# PowerBreakout.net
KiCad netlist of a schematic drawn in Altium Designer
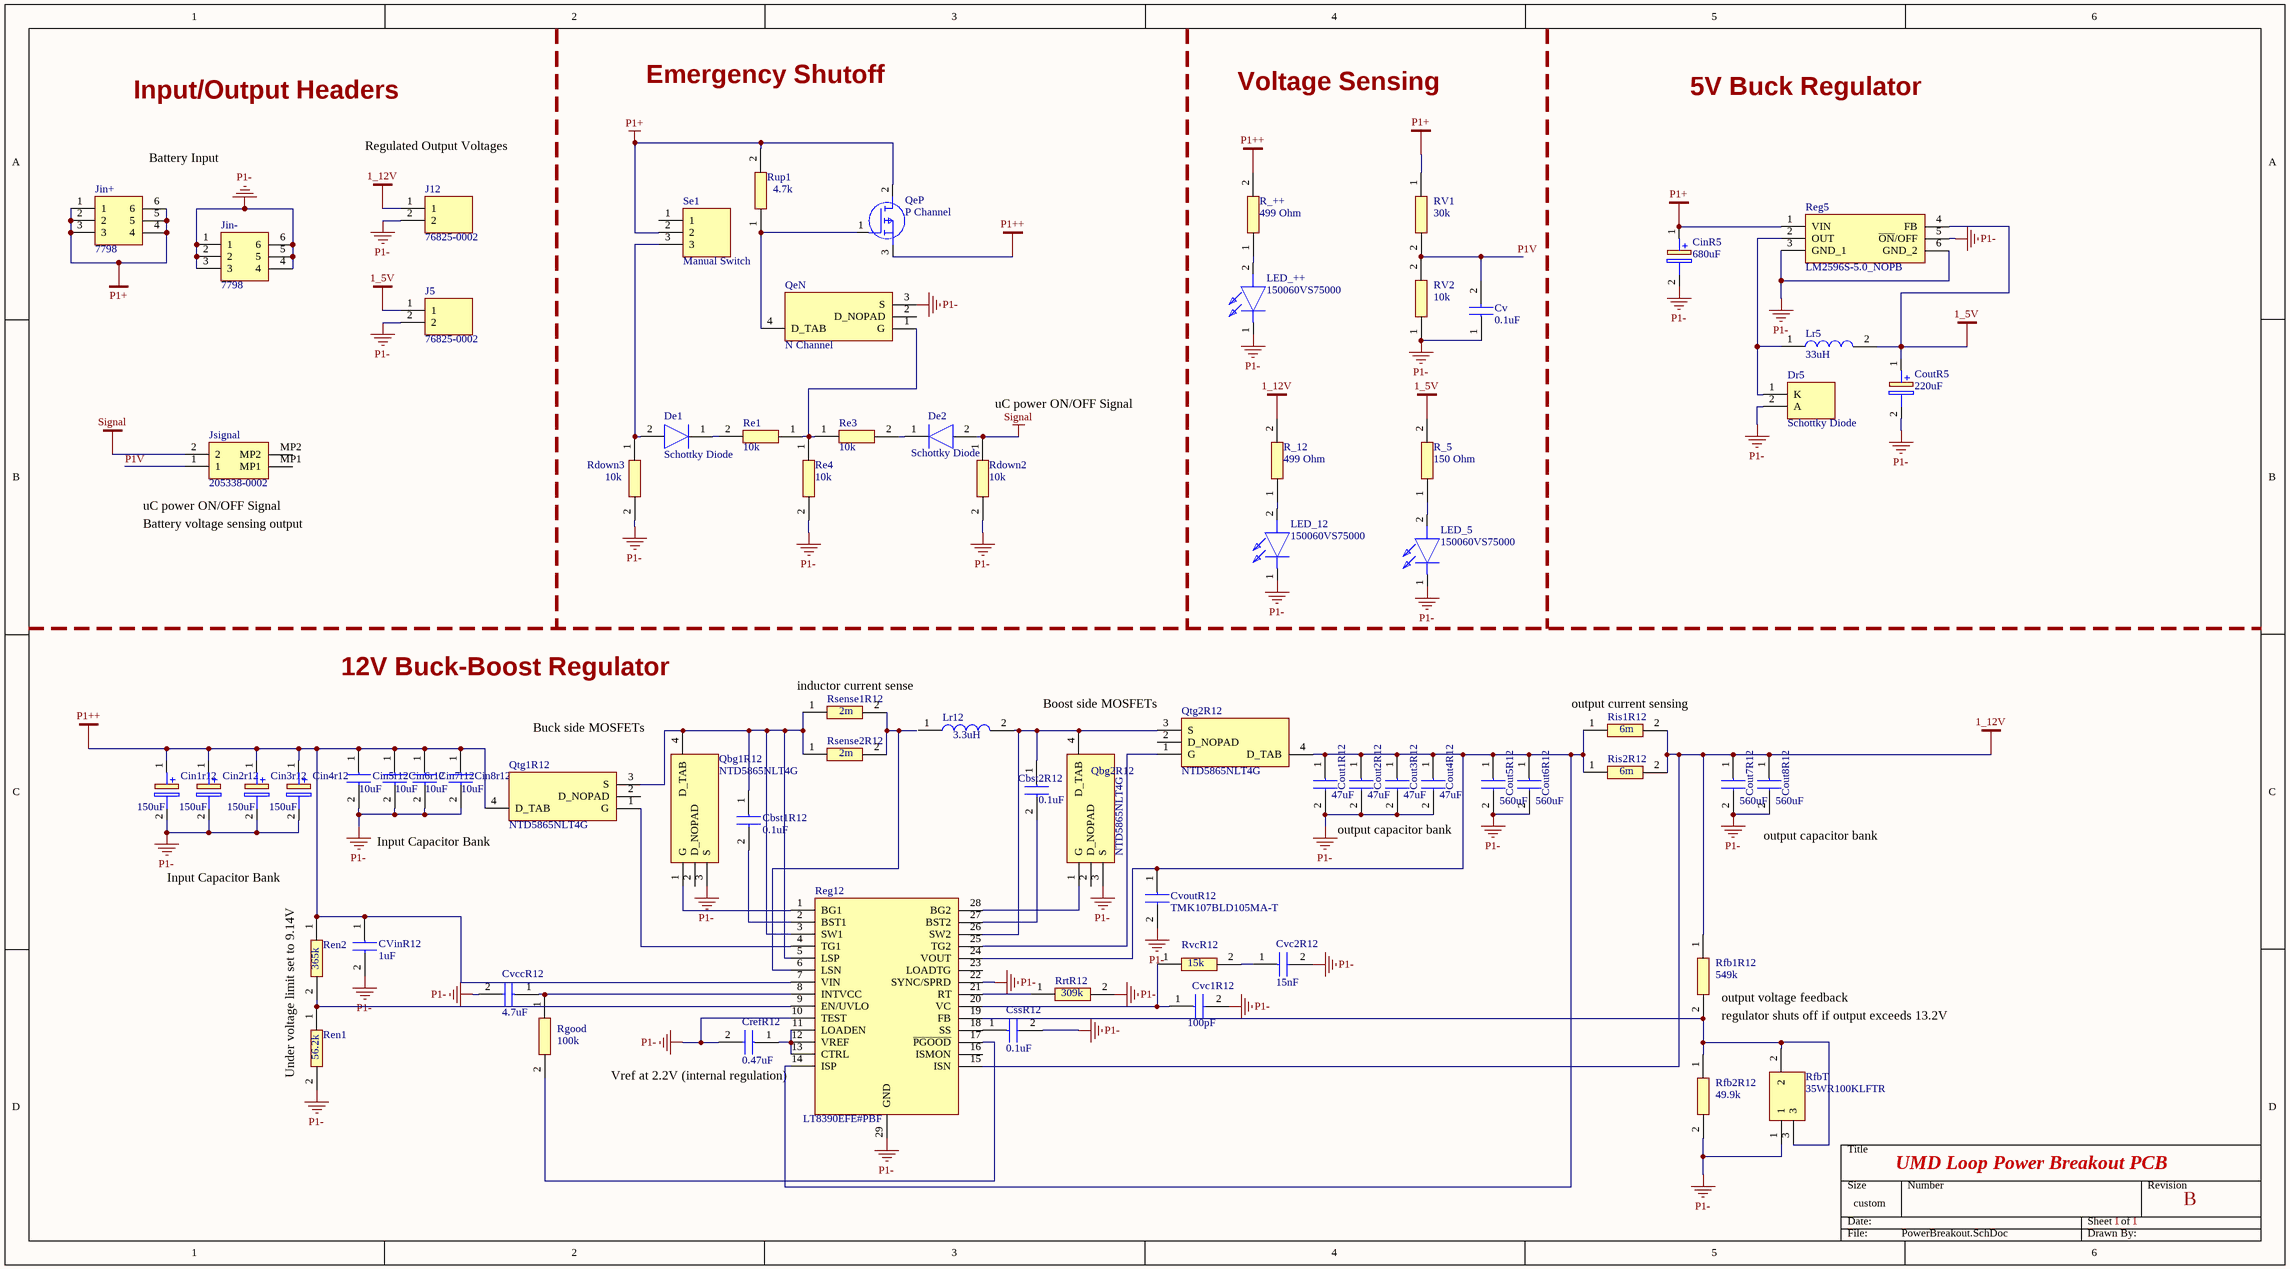
[diagram p0: PowerBreakout.SchDoc]

(export (version "E")
  (design (tool "Eeschema 10.0.6"))
  (components
    (comp (ref "Cbst1R12")
      (value "0.1uF")
      (footprint "PaS_PcbLib:CAPC1608X90N")
      (description "Capacitor")
      (fields
        (field (name "MANUFACTURER_PART_NUMBER") "06033C104J4Z2A")
        (field (name "MOUSER PART NUMBER") "581-06033C104J4Z2A")
      )
      (libsource (lib "PaS_Schlib") (part "06033C104J4Z2A"))
    )
    (comp (ref "Cbst2R12")
      (value "0.1uF")
      (footprint "PaS_PcbLib:CAPC1608X90N")
      (description "Capacitor")
      (fields
        (field (name "MANUFACTURER_PART_NUMBER") "06033C104J4Z2A")
        (field (name "MOUSER PART NUMBER") "581-06033C104J4Z2A")
      )
      (libsource (lib "PaS_Schlib") (part "06033C104J4Z2A"))
    )
    (comp (ref "Cin1r12")
      (value "150uF")
      (footprint "PaS_PcbLib:CAPAE1030X1650N")
      (description "Capacitor Polarised")
      (fields
        (field (name "MANUFACTURER_PART_NUMBER") "EEH-ZS1J151P")
        (field (name "MOUSER PART NUMBER") "667-EEH-ZS1J151P")
      )
      (libsource (lib "PaS_Schlib") (part "EEH-ZS1J151P"))
    )
    (comp (ref "Cin2r12")
      (value "150uF")
      (footprint "PaS_PcbLib:CAPAE1030X1650N")
      (description "Capacitor Polarised")
      (fields
        (field (name "MANUFACTURER_PART_NUMBER") "EEH-ZS1J151P")
        (field (name "MOUSER PART NUMBER") "667-EEH-ZS1J151P")
      )
      (libsource (lib "PaS_Schlib") (part "EEH-ZS1J151P"))
    )
    (comp (ref "Cin3r12")
      (value "150uF")
      (footprint "PaS_PcbLib:CAPAE1030X1650N")
      (description "Capacitor Polarised")
      (fields
        (field (name "MANUFACTURER_PART_NUMBER") "EEH-ZS1J151P")
        (field (name "MOUSER PART NUMBER") "667-EEH-ZS1J151P")
      )
      (libsource (lib "PaS_Schlib") (part "EEH-ZS1J151P"))
    )
    (comp (ref "Cin4r12")
      (value "150uF")
      (footprint "PaS_PcbLib:CAPAE1030X1650N")
      (description "Capacitor Polarised")
      (fields
        (field (name "MANUFACTURER_PART_NUMBER") "EEH-ZS1J151P")
        (field (name "MOUSER PART NUMBER") "667-EEH-ZS1J151P")
      )
      (libsource (lib "PaS_Schlib") (part "EEH-ZS1J151P"))
    )
    (comp (ref "Cin5r12")
      (value "10uF")
      (footprint "PaS_PcbLib:CAPC3225X280N")
      (description "Capacitor")
      (fields
        (field (name "MANUFACTURER_PART_NUMBER") "UMR325AC7106KM-P")
        (field (name "MOUSER PART NUMBER") "963-UMR325AC7106KM-P")
      )
      (libsource (lib "PaS_Schlib") (part "UMR325AC7106KM-P"))
    )
    (comp (ref "Cin6r12")
      (value "10uF")
      (footprint "PaS_PcbLib:CAPC3225X280N")
      (description "Capacitor")
      (fields
        (field (name "MANUFACTURER_PART_NUMBER") "UMR325AC7106KM-P")
        (field (name "MOUSER PART NUMBER") "963-UMR325AC7106KM-P")
      )
      (libsource (lib "PaS_Schlib") (part "UMR325AC7106KM-P"))
    )
    (comp (ref "Cin7r12")
      (value "10uF")
      (footprint "PaS_PcbLib:CAPC3225X280N")
      (description "Capacitor")
      (fields
        (field (name "MANUFACTURER_PART_NUMBER") "UMR325AC7106KM-P")
        (field (name "MOUSER PART NUMBER") "963-UMR325AC7106KM-P")
      )
      (libsource (lib "PaS_Schlib") (part "UMR325AC7106KM-P"))
    )
    (comp (ref "Cin8r12")
      (value "10uF")
      (footprint "PaS_PcbLib:CAPC3225X280N")
      (description "Capacitor")
      (fields
        (field (name "MANUFACTURER_PART_NUMBER") "UMR325AC7106KM-P")
        (field (name "MOUSER PART NUMBER") "963-UMR325AC7106KM-P")
      )
      (libsource (lib "PaS_Schlib") (part "UMR325AC7106KM-P"))
    )
    (comp (ref "CinR5")
      (value "680uF")
      (footprint "PaS_PcbLib:CAPAE1030X1050N")
      (description "Capacitor Polarised")
      (fields
        (field (name "MANUFACTURER_PART_NUMBER") "EEE-FK1C681GP")
        (field (name "MOUSER PART NUMBER") "667-EEE-FK1C681GP")
      )
      (libsource (lib "PaS_Schlib") (part "EEE-FK1C681GP"))
    )
    (comp (ref "Cout1R12")
      (value "47uF")
      (footprint "PaS_PcbLib:CAPC3216X180N")
      (description "Capacitor")
      (fields
        (field (name "MANUFACTURER_PART_NUMBER") "C3216X5R1E476M160AC")
        (field (name "MOUSER PART NUMBER") "810-C3216X5R1E476M")
      )
      (libsource (lib "PaS_Schlib") (part "C3216X5R1E476M160AC"))
    )
    (comp (ref "Cout2R12")
      (value "47uF")
      (footprint "PaS_PcbLib:CAPC3216X180N")
      (description "Capacitor")
      (fields
        (field (name "MANUFACTURER_PART_NUMBER") "C3216X5R1E476M160AC")
        (field (name "MOUSER PART NUMBER") "810-C3216X5R1E476M")
      )
      (libsource (lib "PaS_Schlib") (part "C3216X5R1E476M160AC"))
    )
    (comp (ref "Cout3R12")
      (value "47uF")
      (footprint "PaS_PcbLib:CAPC3216X180N")
      (description "Capacitor")
      (fields
        (field (name "MANUFACTURER_PART_NUMBER") "C3216X5R1E476M160AC")
        (field (name "MOUSER PART NUMBER") "810-C3216X5R1E476M")
      )
      (libsource (lib "PaS_Schlib") (part "C3216X5R1E476M160AC"))
    )
    (comp (ref "Cout4R12")
      (value "47uF")
      (footprint "PaS_PcbLib:CAPC3216X180N")
      (description "Capacitor")
      (fields
        (field (name "MANUFACTURER_PART_NUMBER") "C3216X5R1E476M160AC")
        (field (name "MOUSER PART NUMBER") "810-C3216X5R1E476M")
      )
      (libsource (lib "PaS_Schlib") (part "C3216X5R1E476M160AC"))
    )
    (comp (ref "Cout5R12")
      (value "560uF")
      (footprint "PaS_PcbLib:CAPAE830X1050N")
      (description "Capacitor")
      (fields
        (field (name "MANUFACTURER_PART_NUMBER") "EEE-FT1E561UP")
        (field (name "MOUSER PART NUMBER") "667-EEE-FT1E561UP")
      )
      (libsource (lib "PaS_Schlib") (part "EEE-FT1E561UP"))
    )
    (comp (ref "Cout6R12")
      (value "560uF")
      (footprint "PaS_PcbLib:CAPAE830X1050N")
      (description "Capacitor")
      (fields
        (field (name "MANUFACTURER_PART_NUMBER") "EEE-FT1E561UP")
        (field (name "MOUSER PART NUMBER") "667-EEE-FT1E561UP")
      )
      (libsource (lib "PaS_Schlib") (part "EEE-FT1E561UP"))
    )
    (comp (ref "Cout7R12")
      (value "560uF")
      (footprint "PaS_PcbLib:CAPAE830X1050N")
      (description "Capacitor")
      (fields
        (field (name "MANUFACTURER_PART_NUMBER") "EEE-FT1E561UP")
        (field (name "MOUSER PART NUMBER") "667-EEE-FT1E561UP")
      )
      (libsource (lib "PaS_Schlib") (part "EEE-FT1E561UP"))
    )
    (comp (ref "Cout8R12")
      (value "560uF")
      (footprint "PaS_PcbLib:CAPAE830X1050N")
      (description "Capacitor")
      (fields
        (field (name "MANUFACTURER_PART_NUMBER") "EEE-FT1E561UP")
        (field (name "MOUSER PART NUMBER") "667-EEE-FT1E561UP")
      )
      (libsource (lib "PaS_Schlib") (part "EEE-FT1E561UP"))
    )
    (comp (ref "CoutR5")
      (value "220uF")
      (footprint "PaS_PcbLib:CAPAE660X800N")
      (description "Capacitor Polarised")
      (fields
        (field (name "MANUFACTURER_PART_NUMBER") "EEE-FKA221XAP")
        (field (name "MOUSER PART NUMBER") "667-EEE-FKA221XAP")
      )
      (libsource (lib "PaS_Schlib") (part "EEE-FKA221XAP"))
    )
    (comp (ref "CrefR12")
      (value "0.47uF")
      (footprint "PaS_PcbLib:CAPC2012X140N")
      (description "Capacitor")
      (fields
        (field (name "MANUFACTURER_PART_NUMBER") "08053C474KAT2A")
        (field (name "MOUSER PART NUMBER") "581-08053C474KAT2A")
      )
      (libsource (lib "PaS_Schlib") (part "08053C474KAT2A"))
    )
    (comp (ref "CssR12")
      (value "0.1uF")
      (footprint "PaS_PcbLib:CAPC1608X90N")
      (description "Capacitor")
      (fields
        (field (name "MANUFACTURER_PART_NUMBER") "06033C104J4Z2A")
        (field (name "MOUSER PART NUMBER") "581-06033C104J4Z2A")
      )
      (libsource (lib "PaS_Schlib") (part "06033C104J4Z2A"))
    )
    (comp (ref "Cv")
      (value "0.1uF")
      (footprint "PaS_PcbLib:CAPC2012X100N")
      (description "Capacitor")
      (fields
        (field (name "MANUFACTURER_PART_NUMBER") "C0805C101FCGACAUTO")
        (field (name "MOUSER PART NUMBER") "80-C0805C101FCGACAUT")
      )
      (libsource (lib "PaS_Schlib") (part "C0805C101FCGACAUTO"))
    )
    (comp (ref "Cvc1R12")
      (value "100pF")
      (footprint "PaS_PcbLib:CAPC2012X88N")
      (description "Capacitor")
      (fields
        (field (name "MANUFACTURER_PART_NUMBER") "C0805C101J5RACTU")
        (field (name "MOUSER PART NUMBER") "80-C0805C101J5R")
      )
      (libsource (lib "PaS_Schlib") (part "C0805C101J5RACTU"))
    )
    (comp (ref "Cvc2R12")
      (value "15nF")
      (footprint "PaS_PcbLib:CAPC2012X88N")
      (description "Capacitor")
      (fields
        (field (name "MANUFACTURER_PART_NUMBER") "C0805C151JAGACTU")
        (field (name "MOUSER PART NUMBER") "80-C0805C151JAGACTU")
      )
      (libsource (lib "PaS_Schlib") (part "C0805C151JAGACTU"))
    )
    (comp (ref "CvccR12")
      (value "4.7uF")
      (footprint "PaS_PcbLib:CAPC3316X195N")
      (description "Capacitor")
      (fields
        (field (name "MANUFACTURER_PART_NUMBER") "C1206X475K3RACAUTO7210")
        (field (name "MOUSER PART NUMBER") "80-C1206X475K3RAUTLR")
      )
      (libsource (lib "PaS_Schlib") (part "C1206X475K3RACAUTO7210"))
    )
    (comp (ref "CVinR12")
      (value "1uF")
      (footprint "PaS_PcbLib:CAPC1608X50N")
      (description "Capacitor")
      (fields
        (field (name "MANUFACTURER_PART_NUMBER") "TMK107BLD105MA-T")
        (field (name "MOUSER PART NUMBER") "963-TMK107BLD105MA-T")
      )
      (libsource (lib "PaS_Schlib") (part "TMK107BLD105MA-T"))
    )
    (comp (ref "CvoutR12")
      (value "TMK107BLD105MA-T")
      (footprint "PaS_PcbLib:CAPC1608X50N")
      (description "Capacitor")
      (fields (field (name "MOUSER PART NUMBER") "963-TMK107BLD105MA-T"))
      (libsource (lib "PaS_Schlib") (part "TMK107BLD105MA-T"))
    )
    (comp (ref "De1")
      (value "Schottky Diode")
      (footprint "SODFL3517X110N")
      (description "Diode")
      (fields
        (field (name "MANUFACTURER_PART_NUMBER") "PMEG4030ER,115")
        (field (name "MOUSER PART NUMBER") "771-PMEG4030ER115")
      )
      (libsource (lib "EShutOff") (part "PMEG4030ER,115"))
    )
    (comp (ref "De2")
      (value "Schottky Diode")
      (footprint "SODFL3517X110N")
      (description "Diode")
      (fields
        (field (name "MANUFACTURER_PART_NUMBER") "PMEG4030ER,115")
        (field (name "MOUSER PART NUMBER") "771-PMEG4030ER115")
      )
      (libsource (lib "EShutOff") (part "PMEG4030ER,115"))
    )
    (comp (ref "Dr5")
      (value "Schottky Diode")
      (footprint "SODFL4725X110N")
      (description "Diode")
      (fields
        (field (name "MANUFACTURER_PART_NUMBER") "PMEG4030EP,115")
        (field (name "MOUSER PART NUMBER") "771-PMEG4030EP,115")
      )
      (libsource (lib "PCB_Project") (part "PMEG4030EP,115"))
    )
    (comp (ref "J5")
      (value "76825-0002")
      (footprint "PaS_PcbLib:768250002")
      (description "Connector")
      (fields (field (name "MOUSER PART NUMBER") "538-76825-0002"))
      (libsource (lib "PaS_Schlib") (part "76825-0002"))
    )
    (comp (ref "J12")
      (value "76825-0002")
      (footprint "PaS_PcbLib:768250002")
      (description "Connector")
      (fields (field (name "MOUSER PART NUMBER") "538-76825-0002"))
      (libsource (lib "PaS_Schlib") (part "76825-0002"))
    )
    (comp (ref "Jin+")
      (value "7798")
      (footprint "PaS_PcbLib:7798")
      (description "Connector")
      (fields (field (name "MOUSER PART NUMBER") "534-7798"))
      (libsource (lib "*") (part "7798"))
    )
    (comp (ref "Jin-")
      (value "7798")
      (footprint "PaS_PcbLib:7798")
      (description "Connector")
      (fields (field (name "MOUSER PART NUMBER") "534-7798"))
      (libsource (lib "*") (part "7798"))
    )
    (comp (ref "Jsignal")
      (value "205338-0002")
      (footprint "PaS_PcbLib:2053380002")
      (description "Connector")
      (fields (field (name "MOUSER PART NUMBER") "538-205338-0002"))
      (libsource (lib "*") (part "205338-0002"))
    )
    (comp (ref "LED_++")
      (value "150060VS75000")
      (footprint "PaS_PcbLib:LEDC1608X80N")
      (description "LED")
      (fields (field (name "MOUSER PART NUMBER") "710-150060VS75000"))
      (libsource (lib "*") (part "150060VS75000"))
    )
    (comp (ref "LED_5")
      (value "150060VS75000")
      (footprint "PaS_PcbLib:LEDC1608X80N")
      (description "LED")
      (fields (field (name "MOUSER PART NUMBER") "710-150060VS75000"))
      (libsource (lib "*") (part "150060VS75000"))
    )
    (comp (ref "LED_12")
      (value "150060VS75000")
      (footprint "PaS_PcbLib:LEDC1608X80N")
      (description "LED")
      (fields (field (name "MOUSER PART NUMBER") "710-150060VS75000"))
      (libsource (lib "*") (part "150060VS75000"))
    )
    (comp (ref "Lr5")
      (value "33uH")
      (footprint "PaS_PcbLib:MSS1210333MEB")
      (description "Inductor")
      (fields
        (field (name "MANUFACTURER_PART_NUMBER") "MSS1210-333MEB")
        (field (name "MOUSER PART NUMBER") "994-MSS1210-333MEB")
      )
      (libsource (lib "PaS_Schlib") (part "MSS1210-333MEB"))
    )
    (comp (ref "Lr12")
      (value "3.3uH")
      (footprint "PaS_PcbLib:INDPM135125X650N")
      (description "Inductor")
      (fields
        (field (name "MANUFACTURER_PART_NUMBER") "SRP1265A-3R3M")
        (field (name "MOUSER PART NUMBER") "652-SRP1265A-3R3M")
      )
      (libsource (lib "PaS_Schlib") (part "SRP1265A-3R3M"))
    )
    (comp (ref "Qbg1R12")
      (value "NTD5865NLT4G")
      (footprint "PaS_PcbLib:TO229P990X238-4N")
      (description "Transistor")
      (fields (field (name "MOUSER PART NUMBER") "863-NTD5865NLT4G"))
      (libsource (lib "PaS_Schlib") (part "NTD5865NLT4G"))
    )
    (comp (ref "Qbg2R12")
      (value "NTD5865NLT4G")
      (footprint "PaS_PcbLib:TO229P990X238-4N")
      (description "Transistor")
      (fields (field (name "MOUSER PART NUMBER") "863-NTD5865NLT4G"))
      (libsource (lib "PaS_Schlib") (part "NTD5865NLT4G"))
    )
    (comp (ref "QeN")
      (value "N Channel")
      (footprint "TO229P990X238-4N")
      (description "Transistor")
      (fields
        (field (name "MANUFACTURER_PART_NUMBER") "NTD5865NLT4G")
        (field (name "MOUSER PART NUMBER") "863-NTD5865NLT4G")
      )
      (libsource (lib "") (part "NTD5865NLT4G_1"))
    )
    (comp (ref "QeP")
      (value "P Channel")
      (footprint "STD36P4LLF6")
      (description "MOSFET (P-Channel)")
      (fields
        (field (name "MANUFACTURER_PART_NUMBER") "STD36P4LLF6")
        (field (name "MOUSER PART NUMBER") "511-STD36P4LLF6")
      )
      (libsource (lib "EShutOff") (part "STD36P4LLF6"))
    )
    (comp (ref "Qtg1R12")
      (value "NTD5865NLT4G")
      (footprint "PaS_PcbLib:TO229P990X238-4N")
      (description "Transistor")
      (fields (field (name "MOUSER PART NUMBER") "863-NTD5865NLT4G"))
      (libsource (lib "") (part "NTD5865NLT4G_1"))
    )
    (comp (ref "Qtg2R12")
      (value "NTD5865NLT4G")
      (footprint "PaS_PcbLib:TO229P990X238-4N")
      (description "Transistor")
      (fields (field (name "MOUSER PART NUMBER") "863-NTD5865NLT4G"))
      (libsource (lib "PaS_Schlib") (part "NTD5865NLT4G"))
    )
    (comp (ref "Rdown2")
      (value "10k")
      (footprint "RESC2012X60N")
      (description "Resistor")
      (fields
        (field (name "MANUFACTURER_PART_NUMBER") "CHP0805-FX-1002ELF")
        (field (name "MOUSER PART NUMBER") "652-CHP0805FX1002ELF")
      )
      (libsource (lib "") (part "CHP0805-FX-1002ELF_1"))
    )
    (comp (ref "Rdown3")
      (value "10k")
      (footprint "RESC2012X60N")
      (description "Resistor")
      (fields
        (field (name "MANUFACTURER_PART_NUMBER") "CHP0805-FX-1002ELF")
        (field (name "MOUSER PART NUMBER") "652-CHP0805FX1002ELF")
      )
      (libsource (lib "") (part "CHP0805-FX-1002ELF_1"))
    )
    (comp (ref "Re1")
      (value "10k")
      (footprint "RESC2012X60N")
      (description "Resistor")
      (fields
        (field (name "MANUFACTURER_PART_NUMBER") "CHP0805-FX-1002ELF")
        (field (name "MOUSER PART NUMBER") "652-CHP0805FX1002ELF")
      )
      (libsource (lib "EShutOff") (part "CHP0805-FX-1002ELF"))
    )
    (comp (ref "Re3")
      (value "10k")
      (footprint "RESC2012X60N")
      (description "Resistor")
      (fields
        (field (name "MANUFACTURER_PART_NUMBER") "CHP0805-FX-1002ELF")
        (field (name "MOUSER PART NUMBER") "652-CHP0805FX1002ELF")
      )
      (libsource (lib "") (part "CHP0805-FX-1002ELF_2"))
    )
    (comp (ref "Re4")
      (value "10k")
      (footprint "RESC2012X60N")
      (description "Resistor")
      (fields
        (field (name "MANUFACTURER_PART_NUMBER") "CHP0805-FX-1002ELF")
        (field (name "MOUSER PART NUMBER") "652-CHP0805FX1002ELF")
      )
      (libsource (lib "") (part "CHP0805-FX-1002ELF_1"))
    )
    (comp (ref "Reg5")
      (value "LM2596S-5.0_NOPB")
      (footprint "PaS_PcbLib:KTT0005B")
      (description "Integrated Circuit")
      (fields
        (field (name "MANUFACTURER_PART_NUMBER") "LM2596S-5.0/NOPB")
        (field (name "MOUSER PART NUMBER") "926-LM2596S-5.0/NOPB")
      )
      (libsource (lib "PaS_Schlib") (part "LM2596S-5.0_NOPB"))
    )
    (comp (ref "Reg12")
      (value "LT8390EFE#PBF")
      (footprint "PaS_PcbLib:SOP65P640X120-29N")
      (description "Integrated Circuit")
      (fields (field (name "MOUSER PART NUMBER") "584-LT8390EFE#PBF"))
      (libsource (lib "PaS_Schlib") (part "LT8390EFE#PBF"))
    )
    (comp (ref "Ren1")
      (value "56.2k")
      (footprint "PaS_PcbLib:RESC3216X60N")
      (description "Resistor")
      (fields
        (field (name "MANUFACTURER_PART_NUMBER") "CRCW120656K2FKEA")
        (field (name "MOUSER PART NUMBER") "71-CRCW1206-56.2K-E3")
      )
      (libsource (lib "PaS_Schlib") (part "CRCW120656K2FKEA"))
    )
    (comp (ref "Ren2")
      (value "365k")
      (footprint "PaS_PcbLib:RESC1608X55N")
      (description "Resistor")
      (fields
        (field (name "MANUFACTURER_PART_NUMBER") "CR0603-FX-3653ELF")
        (field (name "MOUSER PART NUMBER") "652-CR0603FX-3653ELF")
      )
      (libsource (lib "PaS_Schlib") (part "CR0603-FX-3653ELF"))
    )
    (comp (ref "Rfb1R12")
      (value "549k")
      (footprint "PaS_PcbLib:RESC2012X65N")
      (description "Resistor")
      (fields
        (field (name "MANUFACTURER_PART_NUMBER") "RP73D2A1M0BTDF")
        (field (name "MOUSER PART NUMBER") "279-RP73D2A1M0BTDF")
      )
      (libsource (lib "PaS_Schlib") (part "RP73D2A1M0BTDF"))
    )
    (comp (ref "Rfb2R12")
      (value "49.9k")
      (footprint "PaS_PcbLib:RESC2113X66N")
      (description "Resistor")
      (fields
        (field (name "MANUFACTURER_PART_NUMBER") "PFC-W0805LF-03-1073-B")
        (field (name "MOUSER PART NUMBER") "66-PFC08LF107K-B")
      )
      (libsource (lib "PaS_Schlib") (part "PFC-W0805LF-03-1073-B"))
    )
    (comp (ref "RfbT")
      (value "35WR100KLFTR")
      (footprint "PaS_PcbLib:35WR100KLFTR")
      (description "Variable Resistor")
      (fields (field (name "MOUSER PART NUMBER") "858-35WR100KLFTR"))
      (libsource (lib "*") (part "35WR100KLFTR"))
    )
    (comp (ref "Rgood")
      (value "100k")
      (footprint "PaS_PcbLib:RESC3116X65N")
      (description "Resistor")
      (fields
        (field (name "MANUFACTURER_PART_NUMBER") "CMP1206AFX-5601ELF")
        (field (name "MOUSER PART NUMBER") "652-CMP1206AFX-5601L")
      )
      (libsource (lib "PaS_Schlib") (part "CMP1206AFX-5601ELF"))
    )
    (comp (ref "Ris1R12")
      (value "6m")
      (footprint "PaS_PcbLib:FUSC6432X52N")
      (description "Resistor")
      (fields
        (field (name "MANUFACTURER_PART_NUMBER") "PMR100HZPFU6L00")
        (field (name "MOUSER PART NUMBER") "755-PMR100HZPFU6L00")
      )
      (libsource (lib "PaS_Schlib") (part "PMR100HZPFU6L00"))
    )
    (comp (ref "Ris2R12")
      (value "6m")
      (footprint "PaS_PcbLib:FUSC6432X52N")
      (description "Resistor")
      (fields
        (field (name "MANUFACTURER_PART_NUMBER") "PMR100HZPFU6L00")
        (field (name "MOUSER PART NUMBER") "755-PMR100HZPFU6L00")
      )
      (libsource (lib "PaS_Schlib") (part "PMR100HZPFU6L00"))
    )
    (comp (ref "RrtR12")
      (value "309k")
      (footprint "PaS_PcbLib:RESC2012X70N")
      (description "Resistor")
      (fields
        (field (name "MANUFACTURER_PART_NUMBER") "ERJ-6ENF3093V")
        (field (name "MOUSER PART NUMBER") "667-ERJ-6ENF3093V")
      )
      (libsource (lib "PaS_Schlib") (part "ERJ-6ENF3093V"))
    )
    (comp (ref "Rsense1R12")
      (value "2m")
      (footprint "PaS_PcbLib:RESC6432X70N")
      (description "Resistor")
      (fields
        (field (name "MANUFACTURER_PART_NUMBER") "ULRB22512R002FLFSLT")
        (field (name "MOUSER PART NUMBER") "66-ULRB2R002FLFSLT")
      )
      (libsource (lib "PaS_Schlib") (part "ULRB22512R002FLFSLT"))
    )
    (comp (ref "Rsense2R12")
      (value "2m")
      (footprint "PaS_PcbLib:RESC6432X70N")
      (description "Resistor")
      (fields
        (field (name "MANUFACTURER_PART_NUMBER") "ULRB22512R002FLFSLT")
        (field (name "MOUSER PART NUMBER") "66-ULRB2R002FLFSLT")
      )
      (libsource (lib "PaS_Schlib") (part "ULRB22512R002FLFSLT"))
    )
    (comp (ref "Rup1")
      (value "4.7k")
      (footprint "RESC3116X65N")
      (description "Resistor")
      (fields
        (field (name "MANUFACTURER_PART_NUMBER") "CHP1206AFX-4701ELF")
        (field (name "MOUSER PART NUMBER") "652-CHP1206AFX-4701L")
      )
      (libsource (lib "EShutOff") (part "CHP1206AFX-4701ELF"))
    )
    (comp (ref "RV1")
      (value "30k")
      (footprint "PaS_PcbLib:RESC2012X60N")
      (description "Resistor")
      (fields
        (field (name "MANUFACTURER_PART_NUMBER") "CRCW080530K0FKEAC")
        (field (name "MOUSER PART NUMBER") "71-CRCW080530K0FKEAC")
      )
      (libsource (lib "PaS_Schlib") (part "CRCW080530K0FKEAC"))
    )
    (comp (ref "RV2")
      (value "10k")
      (footprint "PaS_PcbLib:RESC2012X60N")
      (description "Resistor")
      (fields
        (field (name "MANUFACTURER_PART_NUMBER") "CHP0805-FX-1002ELF")
        (field (name "MOUSER PART NUMBER") "652-CHP0805FX1002ELF")
      )
      (libsource (lib "PaS_Schlib") (part "CHP0805-FX-1002ELF"))
    )
    (comp (ref "RvcR12")
      (value "15k")
      (footprint "PaS_PcbLib:RESC1608X55N")
      (description "Resistor")
      (fields
        (field (name "MANUFACTURER_PART_NUMBER") "ERA-3VEB1502V")
        (field (name "MOUSER PART NUMBER") "667-ERA-3VEB1502V")
      )
      (libsource (lib "PaS_Schlib") (part "ERA-3VEB1502V"))
    )
    (comp (ref "R_++")
      (value "499 Ohm")
      (footprint "PaS_PcbLib:RESC2012X60N")
      (description "Resistor")
      (fields (field (name "MANUFACTURER_PART_NUMBER") "RK73H2ATTD4990F"))
      (libsource (lib "*") (part "RK73H2ATTD4990F"))
    )
    (comp (ref "R_5")
      (value "150 Ohm")
      (footprint "PaS_PcbLib:RESC2012X60N")
      (description "Resistor")
      (fields
        (field (name "MANUFACTURER_PART_NUMBER") "RK73H2ATTD1500F")
        (field (name "MOUSER PART NUMBER") "660-RK73H2ATTD1500F")
      )
      (libsource (lib "*") (part "RK73H2ATTD1500F"))
    )
    (comp (ref "R_12")
      (value "499 Ohm")
      (footprint "PaS_PcbLib:RESC2012X60N")
      (description "Resistor")
      (fields (field (name "MANUFACTURER_PART_NUMBER") "RK73H2ATTD4990F"))
      (libsource (lib "*") (part "RK73H2ATTD4990F"))
    )
    (comp (ref "Se1")
      (value "Manual Switch")
      (footprint "2M1SP3T1B1M2QE")
      (description "Switch")
      (fields
        (field (name "MANUFACTURER_PART_NUMBER") "2M1-SP1-T1-B1-M2QE")
        (field (name "MOUSER PART NUMBER") "691-2M1-SP1-T1B1M2QE")
      )
      (libsource (lib "PCB_Project") (part "2M1-SP1-T1-B1-M2QE"))
    )
  )
  (nets
    (net (code "1") (name "/P1V") (class "Default")
      (node (ref "Cv") (pin "2") (pinfunction "2_2") (pintype "passive"))
      (node (ref "Jsignal") (pin "1") (pinfunction "1_1") (pintype "passive"))
      (node (ref "RV1") (pin "2") (pinfunction "2_2") (pintype "passive"))
      (node (ref "RV2") (pin "2") (pinfunction "2_2") (pintype "passive"))
    )
    (net (code "2") (name "1_5V") (class "Default")
      (node (ref "CoutR5") (pin "1") (pinfunction "+_1") (pintype "passive"))
      (node (ref "J5") (pin "1") (pinfunction "1_1") (pintype "passive"))
      (node (ref "Lr5") (pin "2") (pinfunction "2_2") (pintype "passive"))
      (node (ref "R_5") (pin "2") (pinfunction "2_2") (pintype "passive"))
      (node (ref "Reg5") (pin "4") (pinfunction "FB_4") (pintype "passive"))
    )
    (net (code "3") (name "1_12V") (class "Default")
      (node (ref "Cout7R12") (pin "1") (pinfunction "+_1") (pintype "passive"))
      (node (ref "Cout8R12") (pin "1") (pinfunction "+_1") (pintype "passive"))
      (node (ref "J12") (pin "1") (pinfunction "1_1") (pintype "passive"))
      (node (ref "R_12") (pin "2") (pinfunction "2_2") (pintype "passive"))
      (node (ref "Reg12") (pin "15") (pinfunction "ISN_15") (pintype "passive"))
      (node (ref "Rfb1R12") (pin "1") (pinfunction "1_1") (pintype "passive"))
      (node (ref "Ris1R12") (pin "2") (pinfunction "2_2") (pintype "passive"))
      (node (ref "Ris2R12") (pin "2") (pinfunction "2_2") (pintype "passive"))
    )
    (net (code "4") (name "Net-(Cout5R12-+)") (class "Default")
      (node (ref "Cout1R12") (pin "1") (pinfunction "1_1") (pintype "passive"))
      (node (ref "Cout2R12") (pin "1") (pinfunction "1_1") (pintype "passive"))
      (node (ref "Cout3R12") (pin "1") (pinfunction "1_1") (pintype "passive"))
      (node (ref "Cout4R12") (pin "1") (pinfunction "1_1") (pintype "passive"))
      (node (ref "Cout5R12") (pin "1") (pinfunction "+_1") (pintype "passive"))
      (node (ref "Cout6R12") (pin "1") (pinfunction "+_1") (pintype "passive"))
      (node (ref "CvoutR12") (pin "1") (pinfunction "1_1") (pintype "passive"))
      (node (ref "Qtg2R12") (pin "4") (pinfunction "D_TAB_4") (pintype "passive"))
      (node (ref "Reg12") (pin "14") (pinfunction "ISP_14") (pintype "passive"))
      (node (ref "Reg12") (pin "24") (pinfunction "VOUT_24") (pintype "passive"))
      (node (ref "Ris1R12") (pin "1") (pinfunction "1_1") (pintype "passive"))
      (node (ref "Ris2R12") (pin "1") (pinfunction "1_1") (pintype "passive"))
    )
    (net (code "5") (name "Net-(Cvc2R12-Pad1)") (class "Default")
      (node (ref "Cvc2R12") (pin "1") (pinfunction "1_1") (pintype "passive"))
      (node (ref "RvcR12") (pin "2") (pinfunction "2_2") (pintype "passive"))
    )
    (net (code "6") (name "Net-(De1-A)") (class "Default")
      (node (ref "De1") (pin "2") (pinfunction "A_2") (pintype "passive"))
      (node (ref "Rdown3") (pin "1") (pinfunction "1_1") (pintype "passive"))
      (node (ref "Se1") (pin "3") (pinfunction "3_3") (pintype "passive"))
    )
    (net (code "7") (name "Net-(De1-K)") (class "Default")
      (node (ref "De1") (pin "1") (pinfunction "K_1") (pintype "passive"))
      (node (ref "Re1") (pin "2") (pinfunction "2_2") (pintype "passive"))
    )
    (net (code "8") (name "Net-(De2-K)") (class "Default")
      (node (ref "De2") (pin "1") (pinfunction "K_1") (pintype "passive"))
      (node (ref "Re3") (pin "2") (pinfunction "2_2") (pintype "passive"))
    )
    (net (code "9") (name "Net-(Dr5-K)") (class "Default")
      (node (ref "Dr5") (pin "1") (pinfunction "K_1") (pintype "passive"))
      (node (ref "Lr5") (pin "1") (pinfunction "1_1") (pintype "passive"))
      (node (ref "Reg5") (pin "2") (pinfunction "OUT_2") (pintype "passive"))
    )
    (net (code "10") (name "Net-(LED_++-A)") (class "Default")
      (node (ref "LED_++") (pin "2") (pinfunction "A_2") (pintype "passive"))
      (node (ref "R_++") (pin "1") (pinfunction "1_1") (pintype "passive"))
    )
    (net (code "11") (name "Net-(LED_5-A)") (class "Default")
      (node (ref "LED_5") (pin "2") (pinfunction "A_2") (pintype "passive"))
      (node (ref "R_5") (pin "1") (pinfunction "1_1") (pintype "passive"))
    )
    (net (code "12") (name "Net-(LED_12-A)") (class "Default")
      (node (ref "LED_12") (pin "2") (pinfunction "A_2") (pintype "passive"))
      (node (ref "R_12") (pin "1") (pinfunction "1_1") (pintype "passive"))
    )
    (net (code "13") (name "Net-(Qbg1R12-D_TAB)") (class "Default")
      (node (ref "Cbst1R12") (pin "1") (pinfunction "1_1") (pintype "passive"))
      (node (ref "Qbg1R12") (pin "4") (pinfunction "D_TAB_4") (pintype "passive"))
      (node (ref "Qtg1R12") (pin "3") (pinfunction "S_3") (pintype "passive"))
      (node (ref "Reg12") (pin "3") (pinfunction "SW1_3") (pintype "passive"))
      (node (ref "Reg12") (pin "5") (pinfunction "LSP_5") (pintype "passive"))
      (node (ref "Rsense1R12") (pin "1") (pinfunction "1_1") (pintype "passive"))
      (node (ref "Rsense2R12") (pin "1") (pinfunction "1_1") (pintype "passive"))
    )
    (net (code "14") (name "Net-(Qbg1R12-G)") (class "Default")
      (node (ref "Qbg1R12") (pin "1") (pinfunction "G_1") (pintype "passive"))
      (node (ref "Reg12") (pin "1") (pinfunction "BG1_1") (pintype "passive"))
    )
    (net (code "15") (name "Net-(Qbg2R12-D_TAB)") (class "Default")
      (node (ref "Cbst2R12") (pin "1") (pinfunction "1_1") (pintype "passive"))
      (node (ref "Lr12") (pin "2") (pinfunction "2_2") (pintype "passive"))
      (node (ref "Qbg2R12") (pin "4") (pinfunction "D_TAB_4") (pintype "passive"))
      (node (ref "Qtg2R12") (pin "3") (pinfunction "S_3") (pintype "passive"))
      (node (ref "Reg12") (pin "26") (pinfunction "SW2_26") (pintype "passive"))
    )
    (net (code "16") (name "Net-(Qbg2R12-G)") (class "Default")
      (node (ref "Qbg2R12") (pin "1") (pinfunction "G_1") (pintype "passive"))
      (node (ref "Reg12") (pin "28") (pinfunction "BG2_28") (pintype "passive"))
    )
    (net (code "17") (name "Net-(QeN-D_TAB)") (class "Default")
      (node (ref "QeN") (pin "4") (pinfunction "D_TAB_4") (pintype "passive"))
      (node (ref "QeP") (pin "1") (pinfunction "G_1") (pintype "passive"))
      (node (ref "Rup1") (pin "1") (pinfunction "1_1") (pintype "passive"))
    )
    (net (code "18") (name "Net-(QeN-G)") (class "Default")
      (node (ref "QeN") (pin "1") (pinfunction "G_1") (pintype "passive"))
      (node (ref "Re1") (pin "1") (pinfunction "1_1") (pintype "passive"))
      (node (ref "Re3") (pin "1") (pinfunction "1_1") (pintype "passive"))
      (node (ref "Re4") (pin "1") (pinfunction "1_1") (pintype "passive"))
    )
    (net (code "19") (name "Net-(Qtg1R12-G)") (class "Default")
      (node (ref "Qtg1R12") (pin "1") (pinfunction "G_1") (pintype "passive"))
      (node (ref "Reg12") (pin "4") (pinfunction "TG1_4") (pintype "passive"))
    )
    (net (code "20") (name "Net-(Qtg2R12-G)") (class "Default")
      (node (ref "Qtg2R12") (pin "1") (pinfunction "G_1") (pintype "passive"))
      (node (ref "Reg12") (pin "25") (pinfunction "TG2_25") (pintype "passive"))
    )
    (net (code "21") (name "Net-(Reg12-BST1)") (class "Default")
      (node (ref "Cbst1R12") (pin "2") (pinfunction "2_2") (pintype "passive"))
      (node (ref "Reg12") (pin "2") (pinfunction "BST1_2") (pintype "passive"))
    )
    (net (code "22") (name "Net-(Reg12-BST2)") (class "Default")
      (node (ref "Cbst2R12") (pin "2") (pinfunction "2_2") (pintype "passive"))
      (node (ref "Reg12") (pin "27") (pinfunction "BST2_27") (pintype "passive"))
    )
    (net (code "23") (name "Net-(Reg12-CTRL)") (class "Default")
      (node (ref "CrefR12") (pin "1") (pinfunction "1_1") (pintype "passive"))
      (node (ref "Reg12") (pin "11") (pinfunction "LOADEN_11") (pintype "passive"))
      (node (ref "Reg12") (pin "12") (pinfunction "VREF_12") (pintype "passive"))
      (node (ref "Reg12") (pin "13") (pinfunction "CTRL_13") (pintype "passive"))
    )
    (net (code "24") (name "Net-(Reg12-EN{slash}UVLO)") (class "Default")
      (node (ref "Reg12") (pin "9") (pinfunction "EN/UVLO_9") (pintype "passive"))
      (node (ref "Ren1") (pin "1") (pinfunction "1_1") (pintype "passive"))
      (node (ref "Ren2") (pin "2") (pinfunction "2_2") (pintype "passive"))
    )
    (net (code "25") (name "Net-(Reg12-FB)") (class "Default")
      (node (ref "Reg12") (pin "19") (pinfunction "FB_19") (pintype "passive"))
      (node (ref "Rfb1R12") (pin "2") (pinfunction "2_2") (pintype "passive"))
      (node (ref "Rfb2R12") (pin "1") (pinfunction "1_1") (pintype "passive"))
      (node (ref "RfbT") (pin "2") (pinfunction "2_2") (pintype "passive"))
      (node (ref "RfbT") (pin "3") (pinfunction "3_3") (pintype "passive"))
    )
    (net (code "26") (name "Net-(Reg12-INTVCC)") (class "Default")
      (node (ref "CvccR12") (pin "1") (pinfunction "1_1") (pintype "passive"))
      (node (ref "Reg12") (pin "8") (pinfunction "INTVCC_8") (pintype "passive"))
      (node (ref "Rgood") (pin "1") (pinfunction "1_1") (pintype "passive"))
    )
    (net (code "27") (name "Net-(Reg12-LSN)") (class "Default")
      (node (ref "Reg12") (pin "6") (pinfunction "LSN_6") (pintype "passive"))
      (node (ref "Rsense1R12") (pin "2") (pinfunction "2_2") (pintype "passive"))
      (node (ref "Rsense2R12") (pin "2") (pinfunction "2_2") (pintype "passive"))
    )
    (net (code "28") (name "Net-(Reg12-RT)") (class "Default")
      (node (ref "Reg12") (pin "21") (pinfunction "RT_21") (pintype "passive"))
      (node (ref "RrtR12") (pin "1") (pinfunction "1_1") (pintype "passive"))
    )
    (net (code "29") (name "Net-(Reg12-SS)") (class "Default")
      (node (ref "CssR12") (pin "1") (pinfunction "1_1") (pintype "passive"))
      (node (ref "Reg12") (pin "18") (pinfunction "SS_18") (pintype "passive"))
    )
    (net (code "30") (name "Net-(Reg12-VC)") (class "Default")
      (node (ref "Cvc1R12") (pin "1") (pinfunction "1_1") (pintype "passive"))
      (node (ref "Reg12") (pin "20") (pinfunction "VC_20") (pintype "passive"))
      (node (ref "RvcR12") (pin "1") (pinfunction "1_1") (pintype "passive"))
    )
    (net (code "31") (name "Net-(Reg12-~{PGOOD})") (class "Default")
      (node (ref "Reg12") (pin "17") (pinfunction "~{PGOOD}_17") (pintype "passive"))
      (node (ref "Rgood") (pin "2") (pinfunction "2_2") (pintype "passive"))
    )
    (net (code "32") (name "P1+") (class "Default")
      (node (ref "CinR5") (pin "1") (pinfunction "+_1") (pintype "passive"))
      (node (ref "Jin+") (pin "1") (pinfunction "1_1") (pintype "passive"))
      (node (ref "Jin+") (pin "2") (pinfunction "2_2") (pintype "passive"))
      (node (ref "Jin+") (pin "3") (pinfunction "3_3") (pintype "passive"))
      (node (ref "Jin+") (pin "4") (pinfunction "4_4") (pintype "passive"))
      (node (ref "Jin+") (pin "5") (pinfunction "5_5") (pintype "passive"))
      (node (ref "Jin+") (pin "6") (pinfunction "6_6") (pintype "passive"))
      (node (ref "QeP") (pin "2") (pinfunction "D_2") (pintype "passive"))
      (node (ref "RV1") (pin "1") (pinfunction "1_1") (pintype "passive"))
      (node (ref "Reg5") (pin "1") (pinfunction "VIN_1") (pintype "passive"))
      (node (ref "Rup1") (pin "2") (pinfunction "2_2") (pintype "passive"))
      (node (ref "Se1") (pin "2") (pinfunction "2_2") (pintype "passive"))
    )
    (net (code "33") (name "P1++") (class "Default")
      (node (ref "CVinR12") (pin "1") (pinfunction "1_1") (pintype "passive"))
      (node (ref "Cin1r12") (pin "1") (pinfunction "+_1") (pintype "passive"))
      (node (ref "Cin2r12") (pin "1") (pinfunction "+_1") (pintype "passive"))
      (node (ref "Cin3r12") (pin "1") (pinfunction "+_1") (pintype "passive"))
      (node (ref "Cin4r12") (pin "1") (pinfunction "+_1") (pintype "passive"))
      (node (ref "Cin5r12") (pin "1") (pinfunction "1_1") (pintype "passive"))
      (node (ref "Cin6r12") (pin "1") (pinfunction "1_1") (pintype "passive"))
      (node (ref "Cin7r12") (pin "1") (pinfunction "1_1") (pintype "passive"))
      (node (ref "Cin8r12") (pin "1") (pinfunction "1_1") (pintype "passive"))
      (node (ref "QeP") (pin "3") (pinfunction "S_3") (pintype "passive"))
      (node (ref "Qtg1R12") (pin "4") (pinfunction "D_TAB_4") (pintype "passive"))
      (node (ref "R_++") (pin "2") (pinfunction "2_2") (pintype "passive"))
      (node (ref "Reg12") (pin "7") (pinfunction "VIN_7") (pintype "passive"))
      (node (ref "Ren2") (pin "1") (pinfunction "1_1") (pintype "passive"))
    )
    (net (code "34") (name "P1-") (class "Default")
      (node (ref "CVinR12") (pin "2") (pinfunction "2_2") (pintype "passive"))
      (node (ref "Cin1r12") (pin "2") (pinfunction "-_2") (pintype "passive"))
      (node (ref "Cin2r12") (pin "2") (pinfunction "-_2") (pintype "passive"))
      (node (ref "Cin3r12") (pin "2") (pinfunction "-_2") (pintype "passive"))
      (node (ref "Cin4r12") (pin "2") (pinfunction "-_2") (pintype "passive"))
      (node (ref "Cin5r12") (pin "2") (pinfunction "2_2") (pintype "passive"))
      (node (ref "Cin6r12") (pin "2") (pinfunction "2_2") (pintype "passive"))
      (node (ref "Cin7r12") (pin "2") (pinfunction "2_2") (pintype "passive"))
      (node (ref "Cin8r12") (pin "2") (pinfunction "2_2") (pintype "passive"))
      (node (ref "CinR5") (pin "2") (pinfunction "-_2") (pintype "passive"))
      (node (ref "Cout1R12") (pin "2") (pinfunction "2_2") (pintype "passive"))
      (node (ref "Cout2R12") (pin "2") (pinfunction "2_2") (pintype "passive"))
      (node (ref "Cout3R12") (pin "2") (pinfunction "2_2") (pintype "passive"))
      (node (ref "Cout4R12") (pin "2") (pinfunction "2_2") (pintype "passive"))
      (node (ref "Cout5R12") (pin "2") (pinfunction "-_2") (pintype "passive"))
      (node (ref "Cout6R12") (pin "2") (pinfunction "-_2") (pintype "passive"))
      (node (ref "Cout7R12") (pin "2") (pinfunction "-_2") (pintype "passive"))
      (node (ref "Cout8R12") (pin "2") (pinfunction "-_2") (pintype "passive"))
      (node (ref "CoutR5") (pin "2") (pinfunction "-_2") (pintype "passive"))
      (node (ref "CrefR12") (pin "2") (pinfunction "2_2") (pintype "passive"))
      (node (ref "CssR12") (pin "2") (pinfunction "2_2") (pintype "passive"))
      (node (ref "Cv") (pin "1") (pinfunction "1_1") (pintype "passive"))
      (node (ref "Cvc1R12") (pin "2") (pinfunction "2_2") (pintype "passive"))
      (node (ref "Cvc2R12") (pin "2") (pinfunction "2_2") (pintype "passive"))
      (node (ref "CvccR12") (pin "2") (pinfunction "2_2") (pintype "passive"))
      (node (ref "CvoutR12") (pin "2") (pinfunction "2_2") (pintype "passive"))
      (node (ref "Dr5") (pin "2") (pinfunction "A_2") (pintype "passive"))
      (node (ref "J12") (pin "2") (pinfunction "2_2") (pintype "passive"))
      (node (ref "J5") (pin "2") (pinfunction "2_2") (pintype "passive"))
      (node (ref "Jin-") (pin "1") (pinfunction "1_1") (pintype "passive"))
      (node (ref "Jin-") (pin "2") (pinfunction "2_2") (pintype "passive"))
      (node (ref "Jin-") (pin "3") (pinfunction "3_3") (pintype "passive"))
      (node (ref "Jin-") (pin "4") (pinfunction "4_4") (pintype "passive"))
      (node (ref "Jin-") (pin "5") (pinfunction "5_5") (pintype "passive"))
      (node (ref "Jin-") (pin "6") (pinfunction "6_6") (pintype "passive"))
      (node (ref "LED_++") (pin "1") (pinfunction "K_1") (pintype "passive"))
      (node (ref "LED_12") (pin "1") (pinfunction "K_1") (pintype "passive"))
      (node (ref "LED_5") (pin "1") (pinfunction "K_1") (pintype "passive"))
      (node (ref "Qbg1R12") (pin "3") (pinfunction "S_3") (pintype "passive"))
      (node (ref "Qbg2R12") (pin "3") (pinfunction "S_3") (pintype "passive"))
      (node (ref "QeN") (pin "3") (pinfunction "S_3") (pintype "passive"))
      (node (ref "RV2") (pin "1") (pinfunction "1_1") (pintype "passive"))
      (node (ref "Rdown2") (pin "2") (pinfunction "2_2") (pintype "passive"))
      (node (ref "Rdown3") (pin "2") (pinfunction "2_2") (pintype "passive"))
      (node (ref "Re4") (pin "2") (pinfunction "2_2") (pintype "passive"))
      (node (ref "Reg12") (pin "10") (pinfunction "TEST_10") (pintype "passive"))
      (node (ref "Reg12") (pin "22") (pinfunction "SYNC/SPRD_22") (pintype "passive"))
      (node (ref "Reg12") (pin "29") (pinfunction "GND_29") (pintype "passive"))
      (node (ref "Reg5") (pin "3") (pinfunction "GND_1_3") (pintype "passive"))
      (node (ref "Reg5") (pin "5") (pinfunction "~{ON}/OFF_5") (pintype "passive"))
      (node (ref "Reg5") (pin "6") (pinfunction "GND_2_6") (pintype "passive"))
      (node (ref "Ren1") (pin "2") (pinfunction "2_2") (pintype "passive"))
      (node (ref "Rfb2R12") (pin "2") (pinfunction "2_2") (pintype "passive"))
      (node (ref "RfbT") (pin "1") (pinfunction "1_1") (pintype "passive"))
      (node (ref "RrtR12") (pin "2") (pinfunction "2_2") (pintype "passive"))
    )
    (net (code "35") (name "Signal") (class "Default")
      (node (ref "De2") (pin "2") (pinfunction "A_2") (pintype "passive"))
      (node (ref "Jsignal") (pin "2") (pinfunction "2_2") (pintype "passive"))
      (node (ref "Rdown2") (pin "1") (pinfunction "1_1") (pintype "passive"))
    )
    (net (code "36") (name "unconnected-(Jsignal-PadMP1)") (class "Default")
      (node (ref "Jsignal") (pin "MP1") (pinfunction "MP1_MP1") (pintype "passive"))
    )
    (net (code "37") (name "unconnected-(Jsignal-PadMP2)") (class "Default")
      (node (ref "Jsignal") (pin "MP2") (pinfunction "MP2_MP2") (pintype "passive"))
    )
    (net (code "38") (name "unconnected-(Lr12-Pad1)") (class "Default")
      (node (ref "Lr12") (pin "1") (pinfunction "1_1") (pintype "passive"))
    )
    (net (code "39") (name "unconnected-(Qbg1R12-D_NOPAD-Pad2)") (class "Default")
      (node (ref "Qbg1R12") (pin "2") (pinfunction "D_NOPAD_2") (pintype "passive"))
    )
    (net (code "40") (name "unconnected-(Qbg2R12-D_NOPAD-Pad2)") (class "Default")
      (node (ref "Qbg2R12") (pin "2") (pinfunction "D_NOPAD_2") (pintype "passive"))
    )
    (net (code "41") (name "unconnected-(QeN-D_NOPAD-Pad2)") (class "Default")
      (node (ref "QeN") (pin "2") (pinfunction "D_NOPAD_2") (pintype "passive"))
    )
    (net (code "42") (name "unconnected-(Qtg1R12-D_NOPAD-Pad2)") (class "Default")
      (node (ref "Qtg1R12") (pin "2") (pinfunction "D_NOPAD_2") (pintype "passive"))
    )
    (net (code "43") (name "unconnected-(Qtg2R12-D_NOPAD-Pad2)") (class "Default")
      (node (ref "Qtg2R12") (pin "2") (pinfunction "D_NOPAD_2") (pintype "passive"))
    )
    (net (code "44") (name "unconnected-(Reg12-ISMON-Pad16)") (class "Default")
      (node (ref "Reg12") (pin "16") (pinfunction "ISMON_16") (pintype "passive"))
    )
    (net (code "45") (name "unconnected-(Reg12-LOADTG-Pad23)") (class "Default")
      (node (ref "Reg12") (pin "23") (pinfunction "LOADTG_23") (pintype "passive"))
    )
    (net (code "46") (name "unconnected-(Se1-Pad1)") (class "Default")
      (node (ref "Se1") (pin "1") (pinfunction "1_1") (pintype "passive"))
    )
  )
)
